# H1FR7x_Backend.net
KiCad netlist of a schematic drawn in Altium Designer
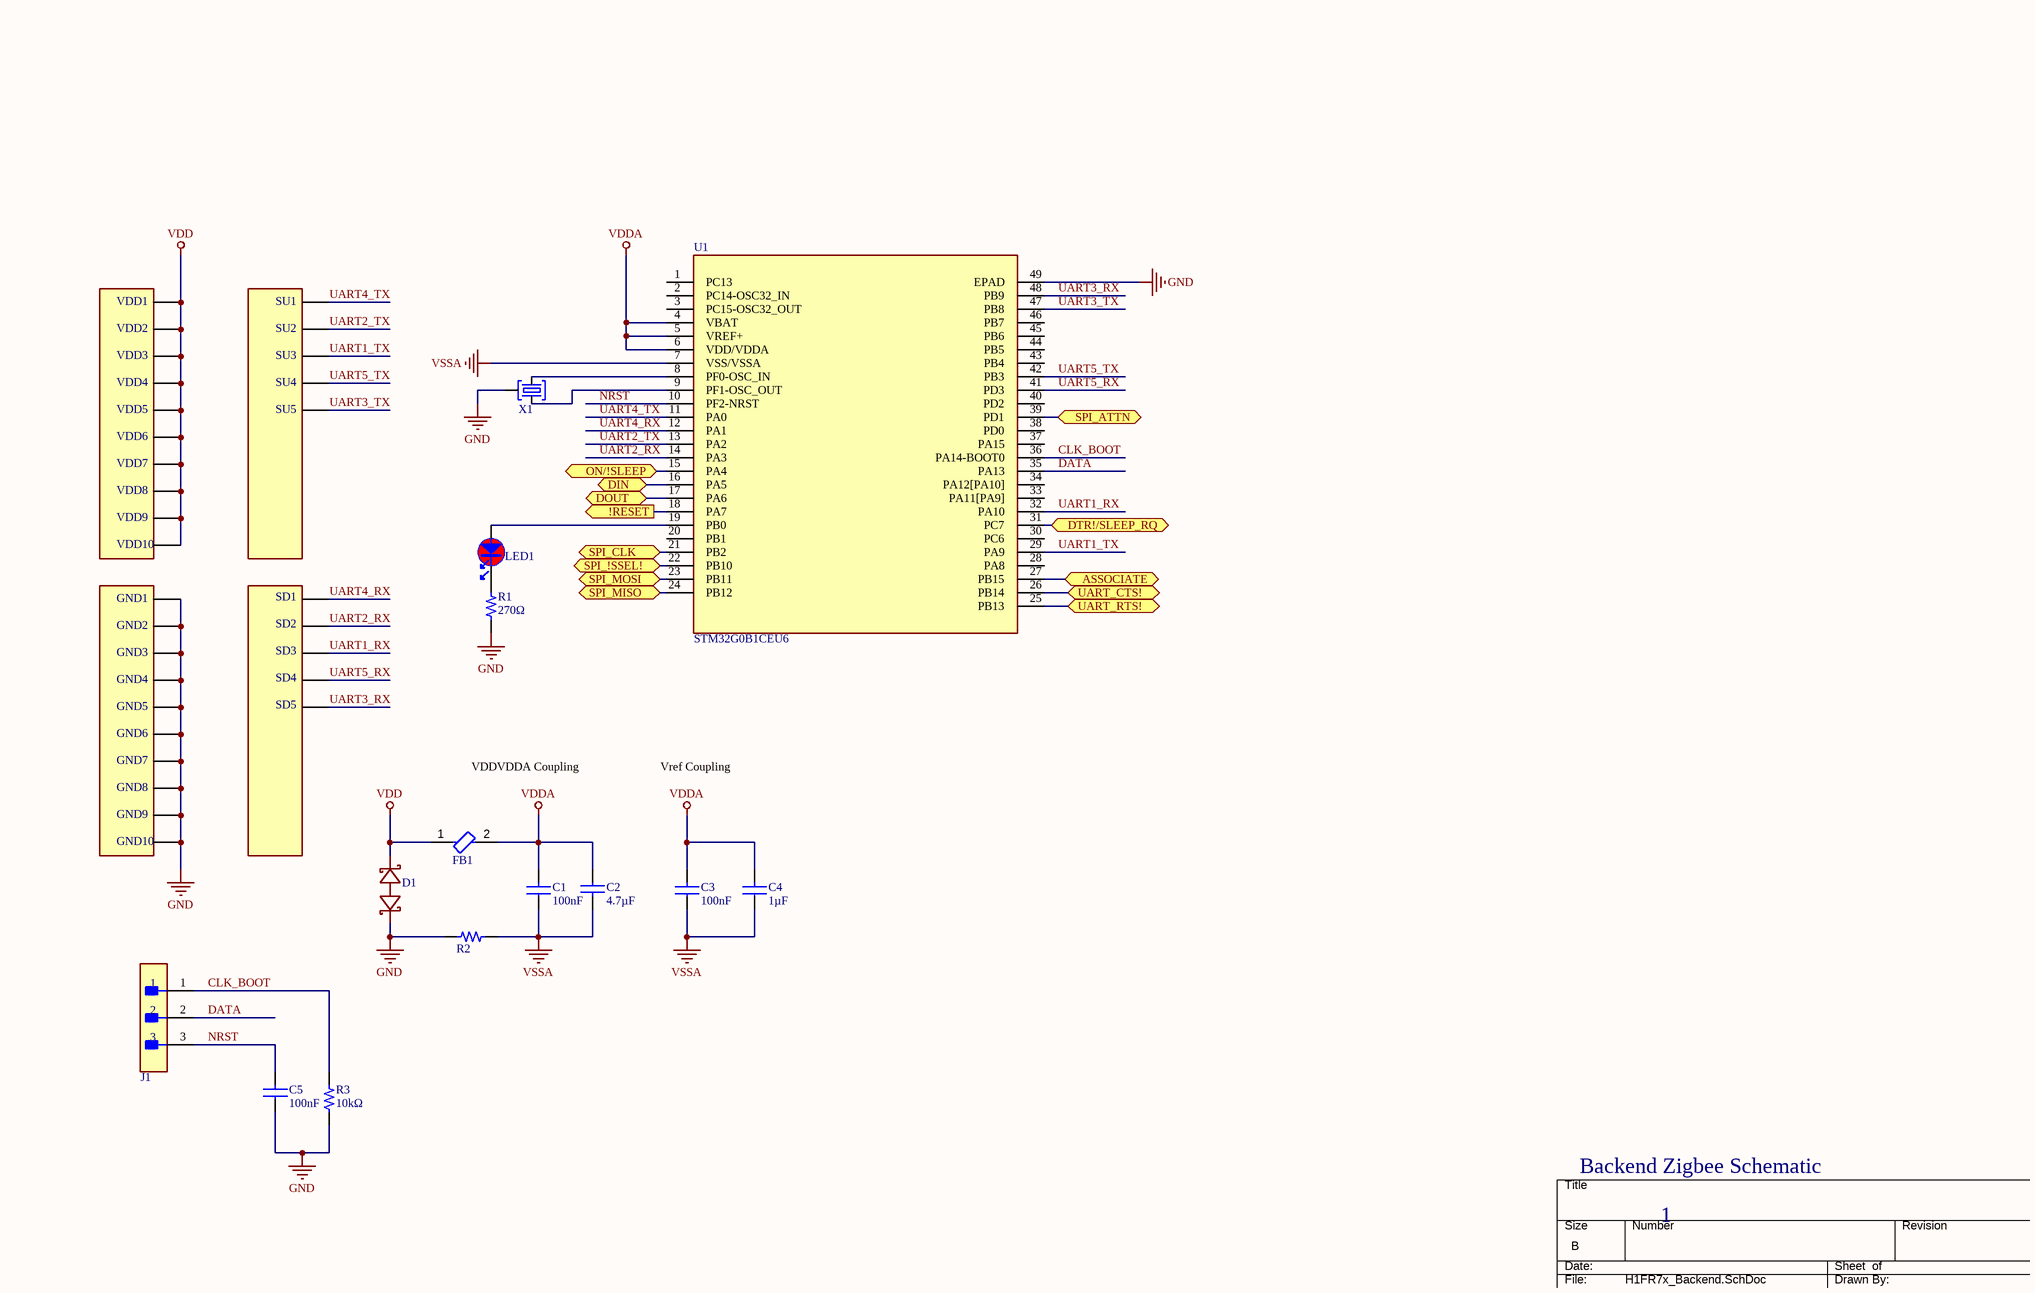
[diagram p0: H1FR7x_Backend.SchDoc]

(export (version "E")
  (design (tool "Eeschema 10.0.6"))
  (components
    (comp (ref "C1")
      (value "100nF")
      (footprint "C0603")
      (fields
        (field (name "MANUFACTURER") "Samsung Electro-Mechanics")
        (field (name "MANUFACTURER PART NUMBER") "CL10B104KA8NNNC")
        (field (name "TOLERANCE") "10%")
      )
      (libsource (lib "Hexabitz Altium Library") (part "generic Capacitor"))
    )
    (comp (ref "C2")
      (value "4.7µF")
      (footprint "C0805")
      (fields
        (field (name "MANUFACTURER") "Samsung Electro-Mechanics")
        (field (name "MANUFACTURER PART NUMBER") "CL21X475KAQNNNE")
        (field (name "TOLERANCE") "10%")
      )
      (libsource (lib "Hexabitz Altium Library") (part "generic Capacitor"))
    )
    (comp (ref "C3")
      (value "100nF")
      (footprint "C0603")
      (fields
        (field (name "MANUFACTURER") "Samsung Electro-Mechanics")
        (field (name "MANUFACTURER PART NUMBER") "CL10B104KA8NNNC")
        (field (name "TOLERANCE") "10%")
      )
      (libsource (lib "Hexabitz Altium Library") (part "generic Capacitor"))
    )
    (comp (ref "C4")
      (value "1µF")
      (footprint "C0805")
      (description "Ceramic Capacitor, Ceramic, 16V, 10% +Tol, 10% -Tol, X7R, 15% TC, 1uF, Surface Mount, 0805")
      (fields
        (field (name "MANUFACTURER") "Yageo Group")
        (field (name "MANUFACTURER PART NUMBER") "CC0805KKX7R7BB105")
      )
      (libsource (lib "Hexabitz Altium Library") (part "generic Capacitor"))
    )
    (comp (ref "C5")
      (value "100nF")
      (footprint "C0603")
      (fields
        (field (name "MANUFACTURER") "Samsung Electro-Mechanics")
        (field (name "MANUFACTURER PART NUMBER") "CL10B104KA8NNNC")
        (field (name "TOLERANCE") "10%")
      )
      (libsource (lib "Hexabitz Altium Library") (part "generic Capacitor"))
    )
    (comp (ref "D1")
      (value "CDSOD323-T03SC")
      (footprint "SOD2513X114N")
      (description "A 3V, 350W, bi-directional, standard capacitance, SOD323 pkg TVS Diode ¦ Bourns CDSOD323-T03SC")
      (fields (field (name "MANUFACTURER") "Bourns"))
      (libsource (lib "Hexabitz Altium Library") (part "CDSOD323-T03SC"))
    )
    (comp (ref "FB1")
      (value "MMZ1608Y300B")
      (footprint "FP-MMZ1608-0_8-MFG")
      (description "Ferrite Beads 0603 30ohms 1500mA Signal Line AEC-Q200")
      (fields
        (field (name "MANUFACTURER") "TDK")
        (field (name "MANUFACTURER PART NUMBER") "MMZ1608Y300BTD25")
      )
      (libsource (lib "Hexabitz Altium Library") (part "MMZ1608Y300B"))
    )
    (comp (ref "GND1")
      (value "HEXABIT_UART_PORT")
      (footprint "HEXABIT_POWER_PORT_D")
      (libsource (lib "hexabitz_connectors.Library") (part "HEXABIT_POWER_PORT_D"))
    )
    (comp (ref "GND2")
      (value "HEXABIT_UART_PORT")
      (footprint "HEXABIT_POWER_PORT_D")
      (libsource (lib "hexabitz_connectors.Library") (part "HEXABIT_POWER_PORT_D"))
    )
    (comp (ref "GND3")
      (value "HEXABIT_UART_PORT")
      (footprint "HEXABIT_POWER_PORT_D_300R")
      (libsource (lib "hexabitz_connectors.Library") (part "HEXABIT_POWER_PORT_D_300R"))
    )
    (comp (ref "GND4")
      (value "HEXABIT_UART_PORT")
      (footprint "HEXABIT_POWER_PORT_D")
      (libsource (lib "hexabitz_connectors.Library") (part "HEXABIT_POWER_PORT_D"))
    )
    (comp (ref "GND5")
      (value "HEXABIT_UART_PORT")
      (footprint "HEXABIT_POWER_PORT_D")
      (libsource (lib "hexabitz_connectors.Library") (part "HEXABIT_POWER_PORT_D"))
    )
    (comp (ref "GND6")
      (value "HEXABIT_UART_PORT")
      (footprint "HEXABIT_POWER_PORT_D")
      (libsource (lib "hexabitz_connectors.Library") (part "HEXABIT_POWER_PORT_D"))
    )
    (comp (ref "GND7")
      (value "HEXABIT_UART_PORT")
      (footprint "HEXABIT_POWER_PORT_D")
      (libsource (lib "hexabitz_connectors.Library") (part "HEXABIT_POWER_PORT_D"))
    )
    (comp (ref "GND8")
      (value "HEXABIT_UART_PORT")
      (footprint "HEXABIT_POWER_PORT_D_300L")
      (libsource (lib "hexabitz_connectors.Library") (part "HEXABIT_POWER_PORT_D_300L"))
    )
    (comp (ref "GND9")
      (value "HEXABIT_UART_PORT")
      (footprint "HEXABIT_POWER_PORT_D")
      (libsource (lib "hexabitz_connectors.Library") (part "HEXABIT_POWER_PORT_D"))
    )
    (comp (ref "GND10")
      (value "HEXABIT_UART_PORT")
      (footprint "HEXABIT_POWER_PORT_D")
      (libsource (lib "hexabitz_connectors.Library") (part "HEXABIT_POWER_PORT_D"))
    )
    (comp (ref "J1")
      (value "TSW-103-14-G-S")
      (footprint "FP-TSW-103-14-G-S-MFG")
      (description "CONN HEADER VERT 3POS 2.54MM")
      (libsource (lib "Altium Content Vault") (part "cd3439d6ef35ae5d9b27ec4fdd3e828"))
    )
    (comp (ref "LED1")
      (value "VLMS1300-GS08")
      (footprint "FP-6_541-5092_01-4-MFG")
      (description "LED Uni-Color Super Red 639nm 2-Pin Chip 0603(1608Metric) T/R")
      (fields (field (name "MANUFACTURER") "Vishay Semiconductors"))
      (libsource (lib "Hexabitz Altium Library") (part "VLMS1300-GS08"))
    )
    (comp (ref "R1")
      (value "270Ω")
      (footprint "R0603")
      (description "Res Thick Film 0603 270 Ohm 5% 0.1W(1/10W) ±200ppm/C Pad SMD Automotive T/R")
      (fields
        (field (name "MANUFACTURER") "Panasonic")
        (field (name "MANUFACTURER PART NUMBER") "ERJ-3GEYJ271V")
      )
      (libsource (lib "") (part "generic Resistor_1"))
    )
    (comp (ref "R2")
      (value "Manufacturer Part Number")
      (footprint "R0603")
      (libsource (lib "Hexabitz Altium Library") (part "generic Resistor"))
    )
    (comp (ref "R3")
      (value "10kΩ")
      (footprint "R0603")
      (description "100mW Thick Film Resistors ±100ppm/℃ ±1% 10kΩ 0603 Chip Resistor - Surface Mount ROHS")
      (fields
        (field (name "MANUFACTURER") "Yageo Group")
        (field (name "MANUFACTURER PART NUMBER") "RC0603FR-0710KL")
      )
      (libsource (lib "") (part "generic Resistor_2"))
    )
    (comp (ref "SD1")
      (value "HEXABIT_UART_PORT")
      (footprint "HEXABIT_UART_PORT_D")
      (libsource (lib "hexabitz_connectors.Library") (part "HEXABIT_UART_PORT_D"))
    )
    (comp (ref "SD2")
      (value "HEXABIT_UART_PORT")
      (footprint "HEXABIT_UART_PORT_D")
      (libsource (lib "hexabitz_connectors.Library") (part "HEXABIT_UART_PORT_D"))
    )
    (comp (ref "SD3")
      (value "HEXABIT_UART_PORT")
      (footprint "HEXABIT_UART_PORT_D")
      (libsource (lib "hexabitz_connectors.Library") (part "HEXABIT_UART_PORT_D"))
    )
    (comp (ref "SD4")
      (value "HEXABIT_UART_PORT")
      (footprint "HEXABIT_UART_PORT_D")
      (libsource (lib "hexabitz_connectors.Library") (part "HEXABIT_UART_PORT_D"))
    )
    (comp (ref "SD5")
      (value "HEXABIT_UART_PORT")
      (footprint "HEXABIT_UART_PORT_D")
      (libsource (lib "hexabitz_connectors.Library") (part "HEXABIT_UART_PORT_D"))
    )
    (comp (ref "SU1")
      (value "HEXABIT_UART_PORT")
      (footprint "HEXABIT_UART_PORT_U")
      (libsource (lib "hexabitz_connectors.Library") (part "HEXABIT_UART_PORT_U"))
    )
    (comp (ref "SU2")
      (value "HEXABIT_UART_PORT")
      (footprint "HEXABIT_UART_PORT_U")
      (libsource (lib "hexabitz_connectors.Library") (part "HEXABIT_UART_PORT_U"))
    )
    (comp (ref "SU3")
      (value "HEXABIT_UART_PORT")
      (footprint "HEXABIT_UART_PORT_U")
      (libsource (lib "hexabitz_connectors.Library") (part "HEXABIT_UART_PORT_U"))
    )
    (comp (ref "SU4")
      (value "HEXABIT_UART_PORT")
      (footprint "HEXABIT_UART_PORT_U")
      (libsource (lib "hexabitz_connectors.Library") (part "HEXABIT_UART_PORT_U"))
    )
    (comp (ref "SU5")
      (value "HEXABIT_UART_PORT")
      (footprint "HEXABIT_UART_PORT_U")
      (libsource (lib "hexabitz_connectors.Library") (part "HEXABIT_UART_PORT_U"))
    )
    (comp (ref "U1")
      (value "STM32G0B1CEU6")
      (footprint "QFN50P700X700X65-49N-D")
      (description "MCU 32-bit ARM Cortex M0+ RISC 512KB Flash 1.8V/2.5V/3.3V 48-Pin UFQFPN EP Tray")
      (fields
        (field (name "MANUFACTURER") "STMicroelectronics")
        (field (name "MANUFACTURER PART NUMBER") "STM32G0B1CEU6")
      )
      (libsource (lib "Hexabitz Altium Library") (part "STM32G0B1CEU6"))
    )
    (comp (ref "VDD1")
      (value "HEXABIT_UART_PORT")
      (footprint "HEXABIT_POWER_PORT_U")
      (libsource (lib "hexabitz_connectors.Library") (part "HEXABIT_POWER_PORT_U"))
    )
    (comp (ref "VDD2")
      (value "HEXABIT_UART_PORT")
      (footprint "HEXABIT_POWER_PORT_U")
      (libsource (lib "hexabitz_connectors.Library") (part "HEXABIT_POWER_PORT_U"))
    )
    (comp (ref "VDD3")
      (value "HEXABIT_UART_PORT")
      (footprint "HEXABIT_POWER_PORT_U_300R")
      (libsource (lib "hexabitz_connectors.Library") (part "HEXABIT_POWER_PORT_U_300R"))
    )
    (comp (ref "VDD4")
      (value "HEXABIT_UART_PORT")
      (footprint "HEXABIT_POWER_PORT_U")
      (libsource (lib "hexabitz_connectors.Library") (part "HEXABIT_POWER_PORT_U"))
    )
    (comp (ref "VDD5")
      (value "HEXABIT_UART_PORT")
      (footprint "HEXABIT_POWER_PORT_U")
      (libsource (lib "hexabitz_connectors.Library") (part "HEXABIT_POWER_PORT_U"))
    )
    (comp (ref "VDD6")
      (value "HEXABIT_UART_PORT")
      (footprint "HEXABIT_POWER_PORT_U")
      (libsource (lib "hexabitz_connectors.Library") (part "HEXABIT_POWER_PORT_U"))
    )
    (comp (ref "VDD7")
      (value "HEXABIT_UART_PORT")
      (footprint "HEXABIT_POWER_PORT_U")
      (libsource (lib "hexabitz_connectors.Library") (part "HEXABIT_POWER_PORT_U"))
    )
    (comp (ref "VDD8")
      (value "HEXABIT_UART_PORT")
      (footprint "HEXABIT_POWER_PORT_U_300L")
      (libsource (lib "hexabitz_connectors.Library") (part "HEXABIT_POWER_PORT_U_300L"))
    )
    (comp (ref "VDD9")
      (value "HEXABIT_UART_PORT")
      (footprint "HEXABIT_POWER_PORT_U")
      (libsource (lib "hexabitz_connectors.Library") (part "HEXABIT_POWER_PORT_U"))
    )
    (comp (ref "VDD10")
      (value "HEXABIT_UART_PORT")
      (footprint "HEXABIT_POWER_PORT_U")
      (libsource (lib "hexabitz_connectors.Library") (part "HEXABIT_POWER_PORT_U"))
    )
    (comp (ref "X1")
      (value "CSTCE8M00G52Z-R0")
      (footprint "XTALL_CSTCE8M00G52")
      (description "Ceramic Resonator 8MHz ±0.5% (Tol) ±0.2% (Stability) 10pF 40Ohm 3-Pin CSMD T/R")
      (fields (field (name "MANUFACTURER") "Murata") (field (name "TOLERANCE") "0.5%"))
      (libsource (lib "Hexabitz Altium Library") (part "CSTCE8M00G52Z-R0"))
    )
  )
  (nets
    (net (code "1") (name "/!RESET") (class "Default")
      (node (ref "U1") (pin "18") (pinfunction "PA7_18") (pintype "passive"))
    )
    (net (code "2") (name "/ASSOCIATE") (class "Default")
      (node (ref "U1") (pin "27") (pinfunction "PB15_27") (pintype "passive"))
    )
    (net (code "3") (name "/CLK_BOOT") (class "Default")
      (node (ref "J1") (pin "1") (pinfunction "1_1") (pintype "passive"))
      (node (ref "R3") (pin "1") (pinfunction "1_1") (pintype "passive"))
      (node (ref "U1") (pin "36") (pinfunction "PA14-BOOT0_36") (pintype "passive"))
    )
    (net (code "4") (name "/DATA") (class "Default")
      (node (ref "J1") (pin "2") (pinfunction "2_2") (pintype "passive"))
      (node (ref "U1") (pin "35") (pinfunction "PA13_35") (pintype "passive"))
    )
    (net (code "5") (name "/DIN") (class "Default")
      (node (ref "U1") (pin "16") (pinfunction "PA5_16") (pintype "passive"))
    )
    (net (code "6") (name "/DOUT") (class "Default")
      (node (ref "U1") (pin "17") (pinfunction "PA6_17") (pintype "passive"))
    )
    (net (code "7") (name "/DTR!{slash}SLEEP_RQ") (class "Default")
      (node (ref "U1") (pin "31") (pinfunction "PC7_31") (pintype "passive"))
    )
    (net (code "8") (name "/NRST") (class "Default")
      (node (ref "C5") (pin "2") (pinfunction "2_2") (pintype "passive"))
      (node (ref "J1") (pin "3") (pinfunction "3_3") (pintype "passive"))
      (node (ref "U1") (pin "10") (pinfunction "PF2-NRST_10") (pintype "passive"))
    )
    (net (code "9") (name "/ON{slash}!SLEEP") (class "Default")
      (node (ref "U1") (pin "15") (pinfunction "PA4_15") (pintype "passive"))
    )
    (net (code "10") (name "/SPI_!SSEL!") (class "Default")
      (node (ref "U1") (pin "22") (pinfunction "PB10_22") (pintype "passive"))
    )
    (net (code "11") (name "/SPI_ATTN") (class "Default")
      (node (ref "U1") (pin "39") (pinfunction "PD1_39") (pintype "passive"))
    )
    (net (code "12") (name "/SPI_CLK") (class "Default")
      (node (ref "U1") (pin "21") (pinfunction "PB2_21") (pintype "passive"))
    )
    (net (code "13") (name "/SPI_MISO") (class "Default")
      (node (ref "U1") (pin "24") (pinfunction "PB12_24") (pintype "passive"))
    )
    (net (code "14") (name "/SPI_MOSI") (class "Default")
      (node (ref "U1") (pin "23") (pinfunction "PB11_23") (pintype "passive"))
    )
    (net (code "15") (name "/UART1_RX") (class "Default")
      (node (ref "SD3") (pin "UART_D") (pinfunction "UART_D_UART_D") (pintype "passive"))
      (node (ref "U1") (pin "32") (pinfunction "PA10_32") (pintype "passive"))
    )
    (net (code "16") (name "/UART1_TX") (class "Default")
      (node (ref "SU3") (pin "UART_U") (pinfunction "UART_U_UART_U") (pintype "passive"))
      (node (ref "U1") (pin "29") (pinfunction "PA9_29") (pintype "passive"))
    )
    (net (code "17") (name "/UART2_RX") (class "Default")
      (node (ref "SD2") (pin "UART_D") (pinfunction "UART_D_UART_D") (pintype "passive"))
      (node (ref "U1") (pin "14") (pinfunction "PA3_14") (pintype "passive"))
    )
    (net (code "18") (name "/UART2_TX") (class "Default")
      (node (ref "SU2") (pin "UART_U") (pinfunction "UART_U_UART_U") (pintype "passive"))
      (node (ref "U1") (pin "13") (pinfunction "PA2_13") (pintype "passive"))
    )
    (net (code "19") (name "/UART3_RX") (class "Default")
      (node (ref "SD5") (pin "UART_D") (pinfunction "UART_D_UART_D") (pintype "passive"))
      (node (ref "U1") (pin "48") (pinfunction "PB9_48") (pintype "passive"))
    )
    (net (code "20") (name "/UART3_TX") (class "Default")
      (node (ref "SU5") (pin "UART_U") (pinfunction "UART_U_UART_U") (pintype "passive"))
      (node (ref "U1") (pin "47") (pinfunction "PB8_47") (pintype "passive"))
    )
    (net (code "21") (name "/UART4_RX") (class "Default")
      (node (ref "SD1") (pin "UART_D") (pinfunction "UART_D_UART_D") (pintype "passive"))
      (node (ref "U1") (pin "12") (pinfunction "PA1_12") (pintype "passive"))
    )
    (net (code "22") (name "/UART4_TX") (class "Default")
      (node (ref "SU1") (pin "UART_U") (pinfunction "UART_U_UART_U") (pintype "passive"))
      (node (ref "U1") (pin "11") (pinfunction "PA0_11") (pintype "passive"))
    )
    (net (code "23") (name "/UART5_RX") (class "Default")
      (node (ref "SD4") (pin "UART_D") (pinfunction "UART_D_UART_D") (pintype "passive"))
      (node (ref "U1") (pin "41") (pinfunction "PD3_41") (pintype "passive"))
    )
    (net (code "24") (name "/UART5_TX") (class "Default")
      (node (ref "SU4") (pin "UART_U") (pinfunction "UART_U_UART_U") (pintype "passive"))
      (node (ref "U1") (pin "42") (pinfunction "PB3_42") (pintype "passive"))
    )
    (net (code "25") (name "/UART_CTS!") (class "Default")
      (node (ref "U1") (pin "26") (pinfunction "PB14_26") (pintype "passive"))
    )
    (net (code "26") (name "/UART_RTS!") (class "Default")
      (node (ref "U1") (pin "25") (pinfunction "PB13_25") (pintype "passive"))
    )
    (net (code "27") (name "GND") (class "Default")
      (node (ref "C5") (pin "1") (pinfunction "1_1") (pintype "passive"))
      (node (ref "D1") (pin "1") (pinfunction "A_1") (pintype "passive"))
      (node (ref "GND1") (pin "Pwr_D") (pinfunction "Pwr_D_Pwr_D") (pintype "passive"))
      (node (ref "GND10") (pin "Pwr_D") (pinfunction "Pwr_D_Pwr_D") (pintype "passive"))
      (node (ref "GND2") (pin "Pwr_D") (pinfunction "Pwr_D_Pwr_D") (pintype "passive"))
      (node (ref "GND3") (pin "Pwr_D") (pinfunction "Pwr_D_Pwr_D") (pintype "passive"))
      (node (ref "GND4") (pin "Pwr_D") (pinfunction "Pwr_D_Pwr_D") (pintype "passive"))
      (node (ref "GND5") (pin "Pwr_D") (pinfunction "Pwr_D_Pwr_D") (pintype "passive"))
      (node (ref "GND6") (pin "Pwr_D") (pinfunction "Pwr_D_Pwr_D") (pintype "passive"))
      (node (ref "GND7") (pin "Pwr_D") (pinfunction "Pwr_D_Pwr_D") (pintype "passive"))
      (node (ref "GND8") (pin "Pwr_D") (pinfunction "Pwr_D_Pwr_D") (pintype "passive"))
      (node (ref "GND9") (pin "Pwr_D") (pinfunction "Pwr_D_Pwr_D") (pintype "passive"))
      (node (ref "R1") (pin "1") (pinfunction "1_1") (pintype "passive"))
      (node (ref "R2") (pin "1") (pinfunction "1_1") (pintype "passive"))
      (node (ref "R3") (pin "2") (pinfunction "2_2") (pintype "passive"))
      (node (ref "U1") (pin "49") (pinfunction "EPAD_49") (pintype "passive"))
      (node (ref "X1") (pin "P$2") (pinfunction "2_P$2") (pintype "passive"))
    )
    (net (code "28") (name "Net-(LED1-Pad1)") (class "Default")
      (node (ref "LED1") (pin "1") (pintype "passive"))
      (node (ref "R1") (pin "2") (pinfunction "2_2") (pintype "passive"))
    )
    (net (code "29") (name "Net-(U1-PB0)") (class "Default")
      (node (ref "LED1") (pin "2") (pintype "passive"))
      (node (ref "U1") (pin "19") (pinfunction "PB0_19") (pintype "passive"))
    )
    (net (code "30") (name "Net-(U1-PF0-OSC_IN)") (class "Default")
      (node (ref "U1") (pin "8") (pinfunction "PF0-OSC_IN_8") (pintype "passive"))
      (node (ref "X1") (pin "P$3") (pinfunction "3_P$3") (pintype "passive"))
    )
    (net (code "31") (name "Net-(U1-PF1-OSC_OUT)") (class "Default")
      (node (ref "U1") (pin "9") (pinfunction "PF1-OSC_OUT_9") (pintype "passive"))
      (node (ref "X1") (pin "P$1") (pinfunction "1_P$1") (pintype "passive"))
    )
    (net (code "32") (name "VDD") (class "Default")
      (node (ref "D1") (pin "2") (pinfunction "C_2") (pintype "passive"))
      (node (ref "FB1") (pin "1") (pinfunction "1_1") (pintype "passive"))
      (node (ref "VDD1") (pin "Pwr_U") (pinfunction "Pwr_U_Pwr_U") (pintype "passive"))
      (node (ref "VDD10") (pin "Pwr_U") (pinfunction "Pwr_U_Pwr_U") (pintype "passive"))
      (node (ref "VDD2") (pin "Pwr_U") (pinfunction "Pwr_U_Pwr_U") (pintype "passive"))
      (node (ref "VDD3") (pin "Pwr_U") (pinfunction "Pwr_U_Pwr_U") (pintype "passive"))
      (node (ref "VDD4") (pin "Pwr_U") (pinfunction "Pwr_U_Pwr_U") (pintype "passive"))
      (node (ref "VDD5") (pin "Pwr_U") (pinfunction "Pwr_U_Pwr_U") (pintype "passive"))
      (node (ref "VDD6") (pin "Pwr_U") (pinfunction "Pwr_U_Pwr_U") (pintype "passive"))
      (node (ref "VDD7") (pin "Pwr_U") (pinfunction "Pwr_U_Pwr_U") (pintype "passive"))
      (node (ref "VDD8") (pin "Pwr_U") (pinfunction "Pwr_U_Pwr_U") (pintype "passive"))
      (node (ref "VDD9") (pin "Pwr_U") (pinfunction "Pwr_U_Pwr_U") (pintype "passive"))
    )
    (net (code "33") (name "VDDA") (class "Default")
      (node (ref "C1") (pin "2") (pinfunction "2_2") (pintype "passive"))
      (node (ref "C2") (pin "1") (pinfunction "1_1") (pintype "passive"))
      (node (ref "C3") (pin "2") (pinfunction "2_2") (pintype "passive"))
      (node (ref "C4") (pin "2") (pinfunction "2_2") (pintype "passive"))
      (node (ref "FB1") (pin "2") (pinfunction "2_2") (pintype "passive"))
      (node (ref "U1") (pin "4") (pinfunction "VBAT_4") (pintype "passive"))
      (node (ref "U1") (pin "5") (pinfunction "VREF+_5") (pintype "passive"))
      (node (ref "U1") (pin "6") (pinfunction "VDD/VDDA_6") (pintype "passive"))
    )
    (net (code "34") (name "VSSA") (class "Default")
      (node (ref "C1") (pin "1") (pinfunction "1_1") (pintype "passive"))
      (node (ref "C2") (pin "2") (pinfunction "2_2") (pintype "passive"))
      (node (ref "C3") (pin "1") (pinfunction "1_1") (pintype "passive"))
      (node (ref "C4") (pin "1") (pinfunction "1_1") (pintype "passive"))
      (node (ref "R2") (pin "2") (pinfunction "2_2") (pintype "passive"))
      (node (ref "U1") (pin "7") (pinfunction "VSS/VSSA_7") (pintype "passive"))
    )
    (net (code "35") (name "unconnected-(U1-PA8-Pad28)") (class "Default")
      (node (ref "U1") (pin "28") (pinfunction "PA8_28") (pintype "passive"))
    )
    (net (code "36") (name "unconnected-(U1-PA11[PA9]-Pad33)") (class "Default")
      (node (ref "U1") (pin "33") (pinfunction "PA11[PA9]_33") (pintype "passive"))
    )
    (net (code "37") (name "unconnected-(U1-PA12[PA10]-Pad34)") (class "Default")
      (node (ref "U1") (pin "34") (pinfunction "PA12[PA10]_34") (pintype "passive"))
    )
    (net (code "38") (name "unconnected-(U1-PA15-Pad37)") (class "Default")
      (node (ref "U1") (pin "37") (pinfunction "PA15_37") (pintype "passive"))
    )
    (net (code "39") (name "unconnected-(U1-PB1-Pad20)") (class "Default")
      (node (ref "U1") (pin "20") (pinfunction "PB1_20") (pintype "passive"))
    )
    (net (code "40") (name "unconnected-(U1-PB4-Pad43)") (class "Default")
      (node (ref "U1") (pin "43") (pinfunction "PB4_43") (pintype "passive"))
    )
    (net (code "41") (name "unconnected-(U1-PB5-Pad44)") (class "Default")
      (node (ref "U1") (pin "44") (pinfunction "PB5_44") (pintype "passive"))
    )
    (net (code "42") (name "unconnected-(U1-PB6-Pad45)") (class "Default")
      (node (ref "U1") (pin "45") (pinfunction "PB6_45") (pintype "passive"))
    )
    (net (code "43") (name "unconnected-(U1-PB7-Pad46)") (class "Default")
      (node (ref "U1") (pin "46") (pinfunction "PB7_46") (pintype "passive"))
    )
    (net (code "44") (name "unconnected-(U1-PC6-Pad30)") (class "Default")
      (node (ref "U1") (pin "30") (pinfunction "PC6_30") (pintype "passive"))
    )
    (net (code "45") (name "unconnected-(U1-PC13-Pad1)") (class "Default")
      (node (ref "U1") (pin "1") (pinfunction "PC13_1") (pintype "passive"))
    )
    (net (code "46") (name "unconnected-(U1-PC14-OSC32_IN-Pad2)") (class "Default")
      (node (ref "U1") (pin "2") (pinfunction "PC14-OSC32_IN_2") (pintype "passive"))
    )
    (net (code "47") (name "unconnected-(U1-PC15-OSC32_OUT-Pad3)") (class "Default")
      (node (ref "U1") (pin "3") (pinfunction "PC15-OSC32_OUT_3") (pintype "passive"))
    )
    (net (code "48") (name "unconnected-(U1-PD0-Pad38)") (class "Default")
      (node (ref "U1") (pin "38") (pinfunction "PD0_38") (pintype "passive"))
    )
    (net (code "49") (name "unconnected-(U1-PD2-Pad40)") (class "Default")
      (node (ref "U1") (pin "40") (pinfunction "PD2_40") (pintype "passive"))
    )
  )
)
